# reader.net
KiCad netlist of a schematic drawn in EAGLE
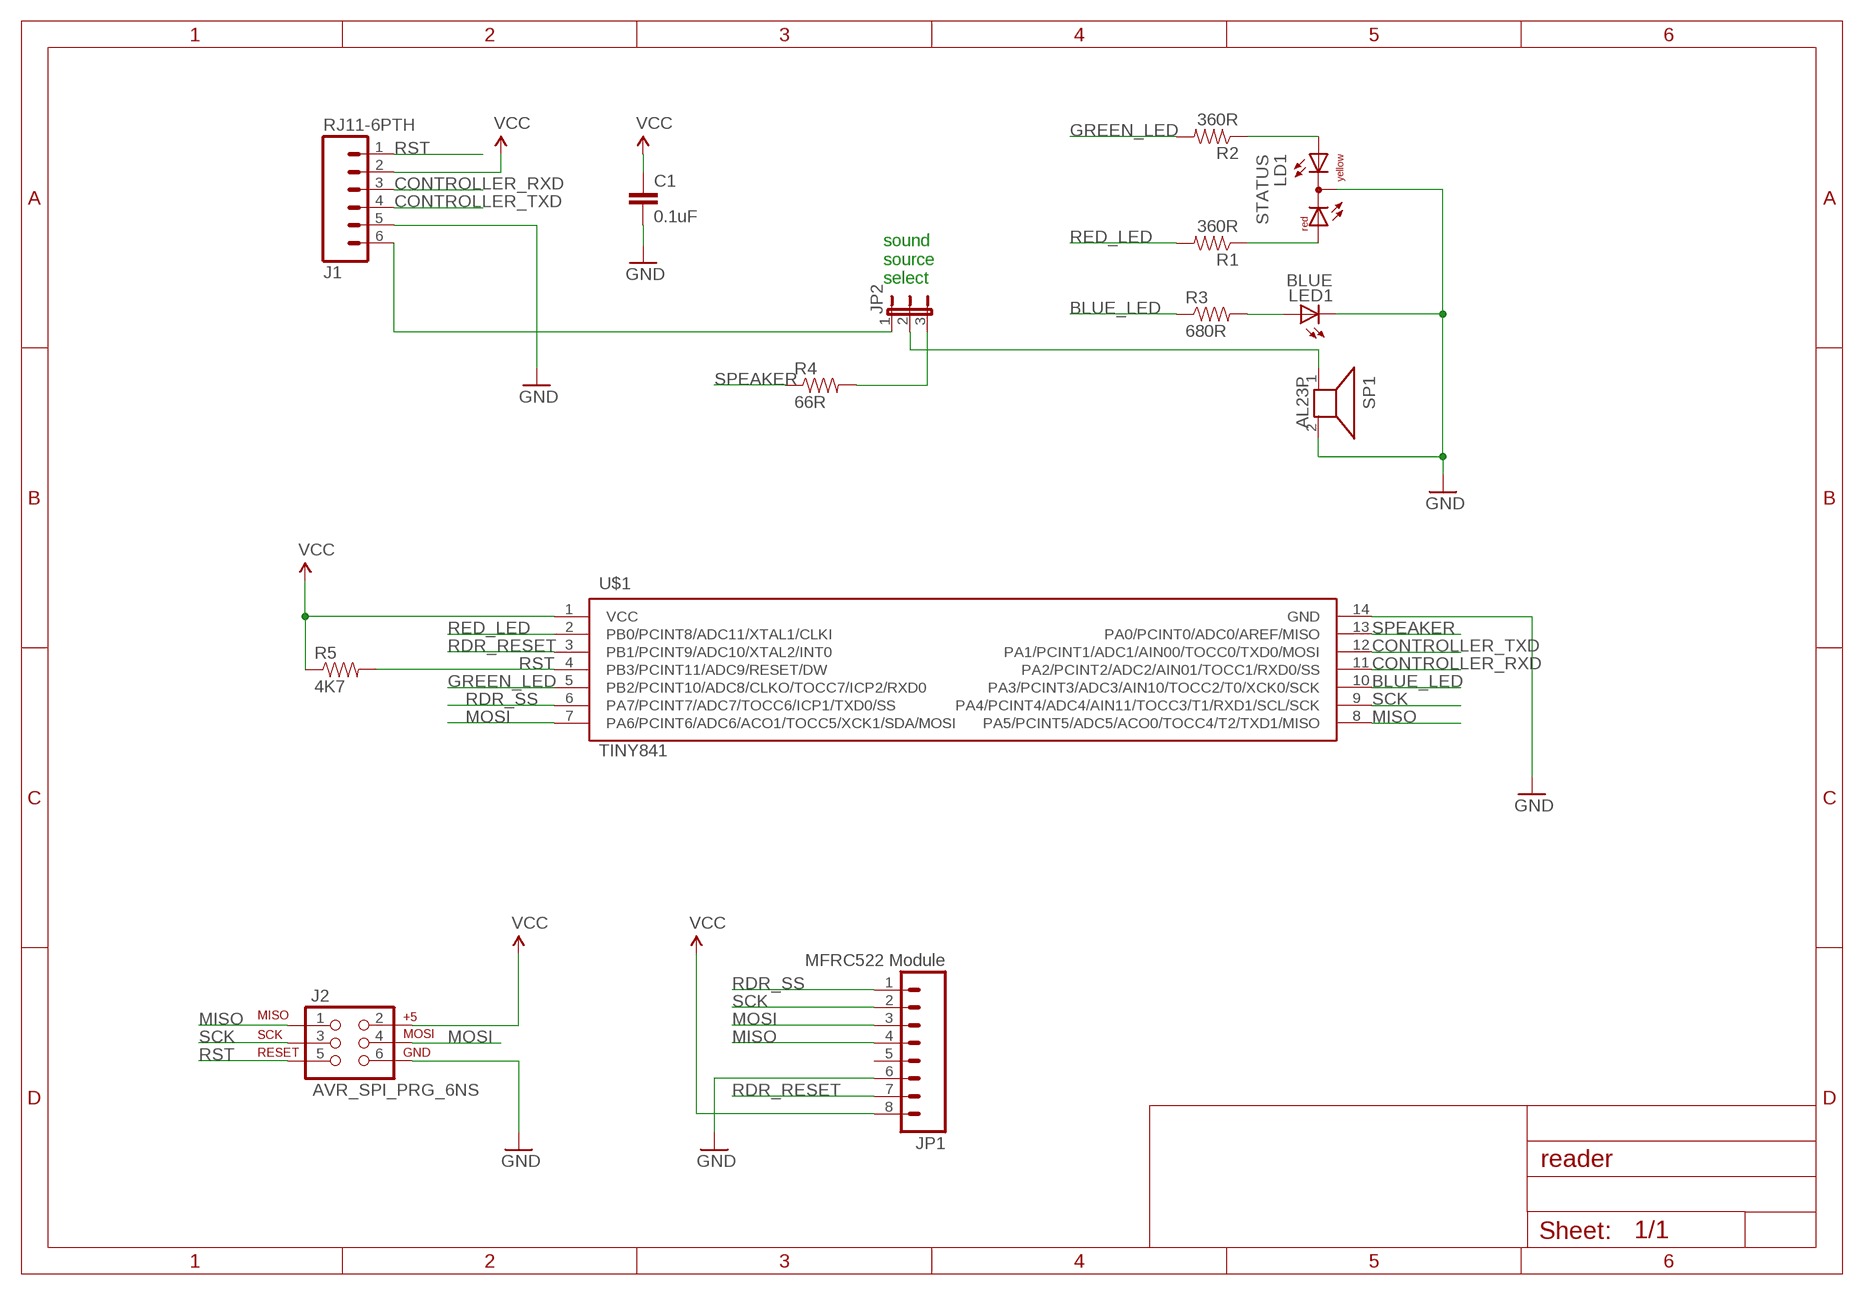
[diagram p0: schematic, sheet 1]

(export (version "E")
  (design (tool "Eeschema 10.0.6"))
  (components
    (comp (ref "C1")
      (value "0.1uF")
      (footprint "eagle-import:CAP-PTH-SMALL-KIT")
      (libsource (lib "eagle-import") (part "0.1UF-50V-20%(PTH)KIT-EZ"))
    )
    (comp (ref "J1")
      (value "RJ11-6PTH")
      (footprint "eagle-import:RJ11-6")
      (libsource (lib "eagle-import") (part "RJ11-6PTH"))
    )
    (comp (ref "J2")
      (value "AVR_SPI_PRG_6NS")
      (footprint "eagle-import:2X3-NS")
      (libsource (lib "eagle-import") (part "AVR_SPI_PRG_6NS"))
    )
    (comp (ref "JP1")
      (value "MFRC522 Module")
      (footprint "eagle-import:1X08")
      (libsource (lib "eagle-import") (part "M081X08"))
    )
    (comp (ref "JP2")
      (value "JP2E")
      (footprint "eagle-import:JP2")
      (libsource (lib "eagle-import") (part "JP2E"))
    )
    (comp (ref "LD1")
      (value "STATUS")
      (footprint "eagle-import:DUOLED-C-5MM")
      (libsource (lib "eagle-import") (part "DUOLED-RY-C"))
    )
    (comp (ref "LED1")
      (value "BLUE")
      (footprint "eagle-import:LED3MM")
      (libsource (lib "eagle-import") (part "LED3MM"))
    )
    (comp (ref "R1")
      (value "360R")
      (footprint "eagle-import:0805")
      (libsource (lib "eagle-import") (part "RESISTOR0805-RES"))
    )
    (comp (ref "R2")
      (value "360R")
      (footprint "eagle-import:0805")
      (libsource (lib "eagle-import") (part "RESISTOR0805-RES"))
    )
    (comp (ref "R3")
      (value "680R")
      (footprint "eagle-import:0805")
      (libsource (lib "eagle-import") (part "RESISTOR0805-RES"))
    )
    (comp (ref "R4")
      (value "66R")
      (footprint "eagle-import:0805")
      (libsource (lib "eagle-import") (part "RESISTOR0805-RES"))
    )
    (comp (ref "R5")
      (value "4K7")
      (footprint "eagle-import:0805")
      (libsource (lib "eagle-import") (part "RESISTOR0805-RES"))
    )
    (comp (ref "SP1")
      (value "AL23P")
      (footprint "eagle-import:AL23P")
      (libsource (lib "eagle-import") (part "AL23P"))
    )
    (comp (ref "U$1")
      (value "TINY841")
      (footprint "eagle-import:SO14")
      (libsource (lib "eagle-import") (part "TINY841"))
    )
  )
  (nets
    (net (code "1") (name "/BLUE_LED") (class "Default")
      (node (ref "R3") (pin "1") (pinfunction "1_1") (pintype "passive"))
      (node (ref "U$1") (pin "10") (pinfunction "PA3/PCINT3/ADC3/AIN10/TOCC2/T0/XCK0/SCK_10") (pintype "bidirectional"))
    )
    (net (code "2") (name "/CONTROLLER_RXD") (class "Default")
      (node (ref "J1") (pin "3") (pinfunction "3_3") (pintype "passive"))
      (node (ref "U$1") (pin "11") (pinfunction "PA2/PCINT2/ADC2/AIN01/TOCC1/RXD0/SS_11") (pintype "bidirectional"))
    )
    (net (code "3") (name "/CONTROLLER_TXD") (class "Default")
      (node (ref "J1") (pin "4") (pinfunction "4_4") (pintype "passive"))
      (node (ref "U$1") (pin "12") (pinfunction "PA1/PCINT1/ADC1/AIN00/TOCC0/TXD0/MOSI_12") (pintype "bidirectional"))
    )
    (net (code "4") (name "/GREEN_LED") (class "Default")
      (node (ref "R2") (pin "2") (pinfunction "2_2") (pintype "passive"))
      (node (ref "U$1") (pin "5") (pinfunction "PB2/PCINT10/ADC8/CLKO/TOCC7/ICP2/RXD0_5") (pintype "bidirectional"))
    )
    (net (code "5") (name "/MISO") (class "Default")
      (node (ref "J2") (pin "1") (pinfunction "1_1") (pintype "passive"))
      (node (ref "JP1") (pin "4") (pinfunction "4_4") (pintype "passive"))
      (node (ref "U$1") (pin "8") (pinfunction "PA5/PCINT5/ADC5/ACO0/TOCC4/T2/TXD1/MISO_8") (pintype "bidirectional"))
    )
    (net (code "6") (name "/MOSI") (class "Default")
      (node (ref "J2") (pin "4") (pinfunction "4_4") (pintype "passive"))
      (node (ref "JP1") (pin "3") (pinfunction "3_3") (pintype "passive"))
      (node (ref "U$1") (pin "7") (pinfunction "PA6/PCINT6/ADC6/ACO1/TOCC5/XCK1/SDA/MOSI_7") (pintype "bidirectional"))
    )
    (net (code "7") (name "/RDR_RESET") (class "Default")
      (node (ref "JP1") (pin "7") (pinfunction "7_7") (pintype "passive"))
      (node (ref "U$1") (pin "3") (pinfunction "PB1/PCINT9/ADC10/XTAL2/INT0_3") (pintype "bidirectional"))
    )
    (net (code "8") (name "/RDR_SS") (class "Default")
      (node (ref "JP1") (pin "1") (pinfunction "1_1") (pintype "passive"))
      (node (ref "U$1") (pin "6") (pinfunction "PA7/PCINT7/ADC7/TOCC6/ICP1/TXD0/SS_6") (pintype "bidirectional"))
    )
    (net (code "9") (name "/RED_LED") (class "Default")
      (node (ref "R1") (pin "2") (pinfunction "2_2") (pintype "passive"))
      (node (ref "U$1") (pin "2") (pinfunction "PB0/PCINT8/ADC11/XTAL1/CLKI_2") (pintype "bidirectional"))
    )
    (net (code "10") (name "/RST") (class "Default")
      (node (ref "J1") (pin "1") (pinfunction "1_1") (pintype "passive"))
      (node (ref "J2") (pin "5") (pinfunction "5_5") (pintype "passive"))
      (node (ref "R5") (pin "2") (pinfunction "2_2") (pintype "passive"))
      (node (ref "U$1") (pin "4") (pinfunction "PB3/PCINT11/ADC9/RESET/DW_4") (pintype "bidirectional"))
    )
    (net (code "11") (name "/SCK") (class "Default")
      (node (ref "J2") (pin "3") (pinfunction "3_3") (pintype "passive"))
      (node (ref "JP1") (pin "2") (pinfunction "2_2") (pintype "passive"))
      (node (ref "U$1") (pin "9") (pinfunction "PA4/PCINT4/ADC4/AIN11/TOCC3/T1/RXD1/SCL/SCK_9") (pintype "bidirectional"))
    )
    (net (code "12") (name "/SPEAKER") (class "Default")
      (node (ref "R4") (pin "1") (pinfunction "1_1") (pintype "passive"))
      (node (ref "U$1") (pin "13") (pinfunction "PA0/PCINT0/ADC0/AREF/MISO_13") (pintype "bidirectional"))
    )
    (net (code "13") (name "GND") (class "Default")
      (node (ref "C1") (pin "2") (pinfunction "2_2") (pintype "passive"))
      (node (ref "J1") (pin "5") (pinfunction "5_5") (pintype "passive"))
      (node (ref "J2") (pin "6") (pinfunction "6_6") (pintype "passive"))
      (node (ref "JP1") (pin "6") (pinfunction "6_6") (pintype "passive"))
      (node (ref "LD1") (pin "C") (pinfunction "C_C") (pintype "passive"))
      (node (ref "LED1") (pin "K") (pinfunction "C_K") (pintype "passive"))
      (node (ref "SP1") (pin "2") (pinfunction "2_2") (pintype "passive"))
      (node (ref "U$1") (pin "14") (pinfunction "GND_14") (pintype "power_in"))
    )
    (net (code "14") (name "Net-(J1-Pad6)") (class "Default")
      (node (ref "J1") (pin "6") (pinfunction "6_6") (pintype "passive"))
      (node (ref "JP2") (pin "1") (pinfunction "1_1") (pintype "passive"))
    )
    (net (code "15") (name "Net-(JP2-Pad2)") (class "Default")
      (node (ref "JP2") (pin "2") (pinfunction "2_2") (pintype "passive"))
      (node (ref "SP1") (pin "1") (pinfunction "1_1") (pintype "passive"))
    )
    (net (code "16") (name "Net-(JP2-Pad3)") (class "Default")
      (node (ref "JP2") (pin "3") (pinfunction "3_3") (pintype "passive"))
      (node (ref "R4") (pin "2") (pinfunction "2_2") (pintype "passive"))
    )
    (net (code "17") (name "Net-(LD1-AY)") (class "Default")
      (node (ref "LD1") (pin "AX") (pinfunction "AY_AX") (pintype "passive"))
      (node (ref "R2") (pin "1") (pinfunction "1_1") (pintype "passive"))
    )
    (net (code "18") (name "Net-(LD1-PadAR)") (class "Default")
      (node (ref "LD1") (pin "AR") (pinfunction "AR_AR") (pintype "passive"))
      (node (ref "R1") (pin "1") (pinfunction "1_1") (pintype "passive"))
    )
    (net (code "19") (name "Net-(LED1-PadA)") (class "Default")
      (node (ref "LED1") (pin "A") (pinfunction "A_A") (pintype "passive"))
      (node (ref "R3") (pin "2") (pinfunction "2_2") (pintype "passive"))
    )
    (net (code "20") (name "VCC") (class "Default")
      (node (ref "C1") (pin "1") (pinfunction "1_1") (pintype "passive"))
      (node (ref "J1") (pin "2") (pinfunction "2_2") (pintype "passive"))
      (node (ref "J2") (pin "2") (pinfunction "2_2") (pintype "passive"))
      (node (ref "JP1") (pin "8") (pinfunction "8_8") (pintype "passive"))
      (node (ref "R5") (pin "1") (pinfunction "1_1") (pintype "passive"))
      (node (ref "U$1") (pin "1") (pinfunction "VCC_1") (pintype "power_in"))
    )
    (net (code "21") (name "unconnected-(JP1-Pad5)") (class "Default")
      (node (ref "JP1") (pin "5") (pinfunction "5_5") (pintype "passive"))
    )
  )
)
